# GVS1_1.net
KiCad netlist of a schematic drawn in EAGLE
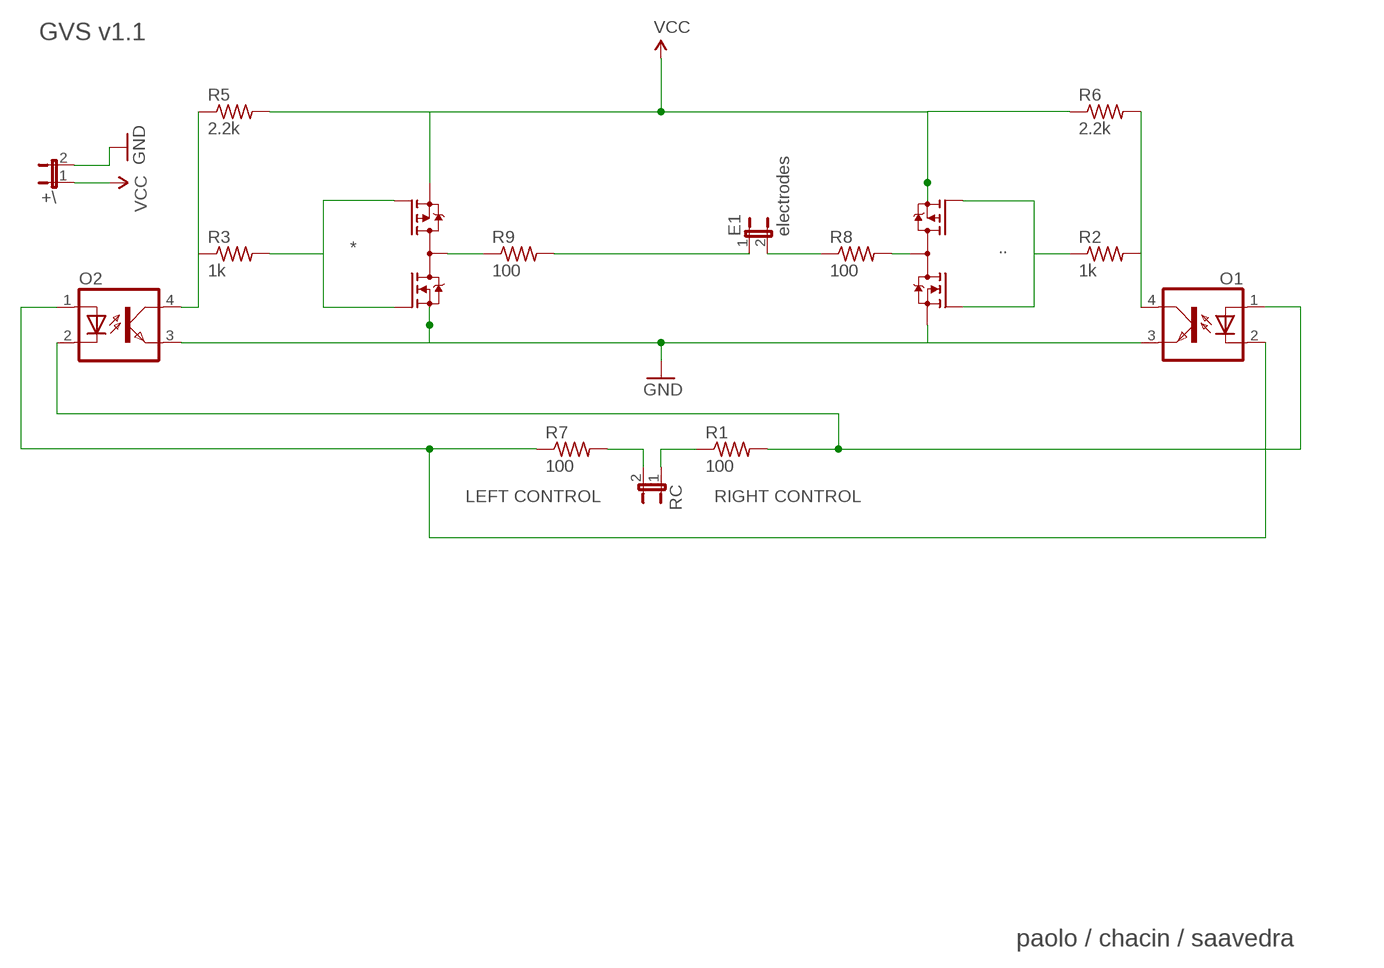
[diagram p0: schematic, sheet 1]

(export (version "E")
  (design (tool "Eeschema 10.0.6"))
  (components
    (comp (ref "*")
      (value "IRF7389")
      (footprint "eagle-import:SO08-IRF")
      (libsource (lib "eagle-import") (part "IRF7389"))
    )
    (comp (ref "+\\")
      (value "JP1E")
      (footprint "eagle-import:JP1")
      (libsource (lib "eagle-import") (part "JP1E"))
    )
    (comp (ref "..")
      (value "IRF7389")
      (footprint "eagle-import:SO08-IRF")
      (libsource (lib "eagle-import") (part "IRF7389"))
    )
    (comp (ref "E1")
      (value "electrodes")
      (footprint "eagle-import:JP1")
      (libsource (lib "eagle-import") (part "JP1E"))
    )
    (comp (ref "O1")
      (value "SFH618A-2")
      (footprint "eagle-import:DIP4")
      (fields (field (name "MF") "VISHAY/TELEFUNKEN"))
      (libsource (lib "eagle-import") (part "SFH618?A-2"))
    )
    (comp (ref "O2")
      (value "SFH618A-2")
      (footprint "eagle-import:DIP4")
      (fields (field (name "MF") "VISHAY/TELEFUNKEN"))
      (libsource (lib "eagle-import") (part "SFH618?A-2"))
    )
    (comp (ref "R1")
      (value "100")
      (footprint "eagle-import:0805-THM-7")
      (libsource (lib "eagle-import") (part "R-US_FLIPFLOP7"))
    )
    (comp (ref "R2")
      (value "1k")
      (footprint "eagle-import:0805-THM-7")
      (libsource (lib "eagle-import") (part "R-US_FLIPFLOP7"))
    )
    (comp (ref "R3")
      (value "1k")
      (footprint "eagle-import:0805-THM-7")
      (libsource (lib "eagle-import") (part "R-US_FLIPFLOP7"))
    )
    (comp (ref "R5")
      (value "2.2k")
      (footprint "eagle-import:0805-THM-7")
      (libsource (lib "eagle-import") (part "R-US_FLIPFLOP7"))
    )
    (comp (ref "R6")
      (value "2.2k")
      (footprint "eagle-import:0805-THM-7")
      (libsource (lib "eagle-import") (part "R-US_FLIPFLOP7"))
    )
    (comp (ref "R7")
      (value "100")
      (footprint "eagle-import:0805-THM-7")
      (libsource (lib "eagle-import") (part "R-US_FLIPFLOP7"))
    )
    (comp (ref "R8")
      (value "100")
      (footprint "eagle-import:0805-THM-7")
      (libsource (lib "eagle-import") (part "R-US_FLIPFLOP7"))
    )
    (comp (ref "R9")
      (value "100")
      (footprint "eagle-import:0805-THM-7")
      (libsource (lib "eagle-import") (part "R-US_FLIPFLOP7"))
    )
    (comp (ref "RC")
      (value "JP1E")
      (footprint "eagle-import:JP1")
      (libsource (lib "eagle-import") (part "JP1E"))
    )
  )
  (nets
    (net (code "1") (name "GND") (class "Default")
      (node (ref "*") (pin "1") (pinfunction "N-S_1") (pintype "passive"))
      (node (ref "+\\") (pin "2") (pinfunction "2_2") (pintype "passive"))
      (node (ref "..") (pin "1") (pinfunction "N-S_1") (pintype "passive"))
      (node (ref "O1") (pin "3") (pinfunction "EMIT_3") (pintype "passive"))
      (node (ref "O2") (pin "3") (pinfunction "EMIT_3") (pintype "passive"))
    )
    (net (code "2") (name "Net-(*-D-Pad5)") (class "Default")
      (node (ref "*") (pin "5") (pinfunction "D_5") (pintype "passive"))
      (node (ref "*") (pin "6") (pinfunction "D_6") (pintype "passive"))
      (node (ref "*") (pin "7") (pinfunction "D_7") (pintype "passive"))
      (node (ref "*") (pin "8") (pinfunction "D_8") (pintype "passive"))
      (node (ref "R9") (pin "1") (pinfunction "1_1") (pintype "passive"))
    )
    (net (code "3") (name "Net-(*-N-G)") (class "Default")
      (node (ref "*") (pin "2") (pinfunction "N-G_2") (pintype "passive"))
      (node (ref "*") (pin "4") (pinfunction "P-G_4") (pintype "passive"))
      (node (ref "R3") (pin "2") (pinfunction "2_2") (pintype "passive"))
    )
    (net (code "4") (name "Net-(..-D-Pad5)") (class "Default")
      (node (ref "..") (pin "5") (pinfunction "D_5") (pintype "passive"))
      (node (ref "..") (pin "6") (pinfunction "D_6") (pintype "passive"))
      (node (ref "..") (pin "7") (pinfunction "D_7") (pintype "passive"))
      (node (ref "..") (pin "8") (pinfunction "D_8") (pintype "passive"))
      (node (ref "R8") (pin "2") (pinfunction "2_2") (pintype "passive"))
    )
    (net (code "5") (name "Net-(..-N-G)") (class "Default")
      (node (ref "..") (pin "2") (pinfunction "N-G_2") (pintype "passive"))
      (node (ref "..") (pin "4") (pinfunction "P-G_4") (pintype "passive"))
      (node (ref "R2") (pin "1") (pinfunction "1_1") (pintype "passive"))
    )
    (net (code "6") (name "Net-(E1-Pad1)") (class "Default")
      (node (ref "E1") (pin "1") (pinfunction "1_1") (pintype "passive"))
      (node (ref "R9") (pin "2") (pinfunction "2_2") (pintype "passive"))
    )
    (net (code "7") (name "Net-(E1-Pad2)") (class "Default")
      (node (ref "E1") (pin "2") (pinfunction "2_2") (pintype "passive"))
      (node (ref "R8") (pin "1") (pinfunction "1_1") (pintype "passive"))
    )
    (net (code "8") (name "Net-(O1-A)") (class "Default")
      (node (ref "O1") (pin "1") (pinfunction "A_1") (pintype "passive"))
      (node (ref "O2") (pin "2") (pinfunction "C_2") (pintype "passive"))
      (node (ref "R1") (pin "2") (pinfunction "2_2") (pintype "passive"))
    )
    (net (code "9") (name "Net-(O1-C)") (class "Default")
      (node (ref "O1") (pin "2") (pinfunction "C_2") (pintype "passive"))
      (node (ref "O2") (pin "1") (pinfunction "A_1") (pintype "passive"))
      (node (ref "R7") (pin "1") (pinfunction "1_1") (pintype "passive"))
    )
    (net (code "10") (name "Net-(O1-COL)") (class "Default")
      (node (ref "O1") (pin "4") (pinfunction "COL_4") (pintype "passive"))
      (node (ref "R2") (pin "2") (pinfunction "2_2") (pintype "passive"))
      (node (ref "R6") (pin "2") (pinfunction "2_2") (pintype "passive"))
    )
    (net (code "11") (name "Net-(O2-COL)") (class "Default")
      (node (ref "O2") (pin "4") (pinfunction "COL_4") (pintype "passive"))
      (node (ref "R3") (pin "1") (pinfunction "1_1") (pintype "passive"))
      (node (ref "R5") (pin "1") (pinfunction "1_1") (pintype "passive"))
    )
    (net (code "12") (name "Net-(R1-Pad1)") (class "Default")
      (node (ref "R1") (pin "1") (pinfunction "1_1") (pintype "passive"))
      (node (ref "RC") (pin "1") (pinfunction "1_1") (pintype "passive"))
    )
    (net (code "13") (name "Net-(R7-Pad2)") (class "Default")
      (node (ref "R7") (pin "2") (pinfunction "2_2") (pintype "passive"))
      (node (ref "RC") (pin "2") (pinfunction "2_2") (pintype "passive"))
    )
    (net (code "14") (name "VCC") (class "Default")
      (node (ref "*") (pin "3") (pinfunction "P-S_3") (pintype "passive"))
      (node (ref "+\\") (pin "1") (pinfunction "1_1") (pintype "passive"))
      (node (ref "..") (pin "3") (pinfunction "P-S_3") (pintype "passive"))
      (node (ref "R5") (pin "2") (pinfunction "2_2") (pintype "passive"))
      (node (ref "R6") (pin "1") (pinfunction "1_1") (pintype "passive"))
    )
  )
)
